# Sheet1.net
KiCad netlist of a schematic drawn in Altium Designer
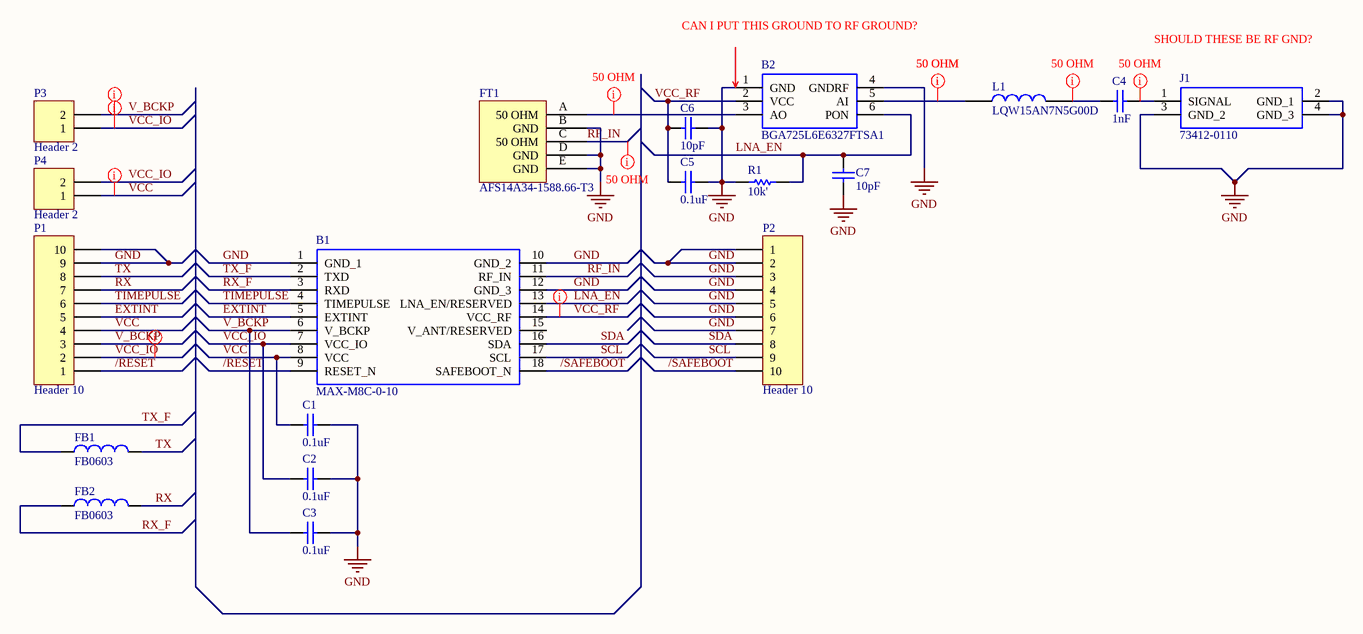
[diagram p0: Sheet1.SchDoc]

(export (version "E")
  (design (tool "Eeschema 10.0.6"))
  (components
    (comp (ref "B1")
      (value "MAX-M8C-0-10")
      (footprint "MAX-M8")
      (description "u-blox M8 concurrent GNSS module")
      (libsource (lib "MAX-M8C-0-10") (part "MAX-M8C-0-10"))
    )
    (comp (ref "B2")
      (value "BGA725L6E6327FTSA1")
      (footprint "BGS12SN6E6327XTSA1")
      (description "INFINEON - BGA725L6E6327FTSA1 - RF AMP, 20DB, 1.615GHZ, 3.6V, TSLP-6")
      (fields (field (name "MOUSER PART NUMBER") "726-BGA725L6E6327FTS"))
      (libsource (lib "BGA725L6E6327FTSA1") (part "BGA725L6E6327FTSA1"))
    )
    (comp (ref "C1")
      (value "0.1uF")
      (footprint "0603CAP")
      (description "0603 Ceramic Chip Capacitor - Standard")
      (fields (field (name "Comment") "C0603"))
      (libsource (lib "Standard Components") (part "C0603"))
    )
    (comp (ref "C2")
      (value "0.1uF")
      (footprint "0603CAP")
      (description "0603 Ceramic Chip Capacitor - Standard")
      (fields (field (name "Comment") "C0603"))
      (libsource (lib "Standard Components") (part "C0603"))
    )
    (comp (ref "C3")
      (value "0.1uF")
      (footprint "0603CAP")
      (description "0603 Ceramic Chip Capacitor - Standard")
      (fields (field (name "Comment") "C0603"))
      (libsource (lib "Standard Components") (part "C0603"))
    )
    (comp (ref "C4")
      (value "1nF")
      (footprint "0603CAP")
      (description "0603 Ceramic Chip Capacitor - Standard")
      (fields (field (name "Comment") "C0603"))
      (libsource (lib "Standard Components") (part "C0603"))
    )
    (comp (ref "C5")
      (value "0.1uF")
      (footprint "0603CAP")
      (description "0603 Ceramic Chip Capacitor - Standard")
      (fields (field (name "Comment") "C0603"))
      (libsource (lib "Standard Components") (part "C0603"))
    )
    (comp (ref "C6")
      (value "10pF")
      (footprint "0603CAP")
      (description "0603 Ceramic Chip Capacitor - Standard")
      (fields (field (name "Comment") "C0603"))
      (libsource (lib "Standard Components") (part "C0603"))
    )
    (comp (ref "C7")
      (value "10pF")
      (footprint "0603CAP")
      (description "0603 Ceramic Chip Capacitor - Standard")
      (fields (field (name "Comment") "C0603"))
      (libsource (lib "Standard Components") (part "C0603"))
    )
    (comp (ref "FB1")
      (value "FB0603")
      (footprint "0603CAP")
      (description "0603 Multilayer Ferrite Power Bead")
      (fields (field (name "MANUFACTURER") "KOA Speer"))
      (libsource (lib "Standard Components") (part "FB0603"))
    )
    (comp (ref "FB2")
      (value "FB0603")
      (footprint "0603CAP")
      (description "0603 Multilayer Ferrite Power Bead")
      (fields (field (name "MANUFACTURER") "KOA Speer"))
      (libsource (lib "Standard Components") (part "FB0603"))
    )
    (comp (ref "FT1")
      (value "AFS14A34-1588.66-T3")
      (footprint "AFS14A34-1588.66-T3")
      (description "SAW FILTER")
      (fields (field (name "MANUFACTURER") "Abracon LLC"))
      (libsource (lib "myLib") (part "AFS14A34-1588.66-T3"))
    )
    (comp (ref "J1")
      (value "73412-0110")
      (footprint "73412-0110")
      (description "50 Ohms, MCRF, PCB Vertical Jack Receptacle, SMT, 1.25mm Mounted Height")
      (fields (field (name "RS PART NUMBER") "1676350") (field (name "MOUSER PART NUMBER") "538-73412-0110"))
      (libsource (lib "73412-0110") (part "73412-0110"))
    )
    (comp (ref "L1")
      (value "LQW15AN7N5G00D")
      (footprint "INDC1005X55N")
      (fields
        (field (name "RS PART NUMBER") "7926473P")
        (field (name "MOUSER PART NUMBER") "81-LQW15AN7N5G00D")
      )
      (libsource (lib "LQW15AN7N5G00D") (part "LQW15AN7N5G00D"))
    )
    (comp (ref "P1")
      (value "Header 10")
      (footprint "HDR1X10")
      (description "Header, 10-Pin")
      (fields (field (name "PUBLISHER") "Altium Limited"))
      (libsource (lib "") (part "Header 10_1"))
    )
    (comp (ref "P2")
      (value "Header 10")
      (footprint "HDR1X10")
      (description "Header, 10-Pin")
      (fields (field (name "PUBLISHER") "Altium Limited"))
      (libsource (lib "Miscellaneous Connectors") (part "Header 10"))
    )
    (comp (ref "P3")
      (value "Header 2")
      (footprint "HDR1X2")
      (description "Header, 2-Pin")
      (fields (field (name "PUBLISHER") "Altium Limited"))
      (libsource (lib "Miscellaneous Connectors") (part "Header 2"))
    )
    (comp (ref "P4")
      (value "Header 2")
      (footprint "HDR1X2")
      (description "Header, 2-Pin")
      (fields (field (name "PUBLISHER") "Altium Limited"))
      (libsource (lib "Miscellaneous Connectors") (part "Header 2"))
    )
    (comp (ref "R1")
      (value "10k'")
      (footprint "0603RES")
      (description "0603 Chip Resistor - Standard")
      (fields (field (name "Comment") "R0603"))
      (libsource (lib "Standard Components") (part "R0603"))
    )
  )
  (nets
    (net (code "1") (name "/EXTINT") (class "Default")
      (node (ref "B1") (pin "5") (pinfunction "EXTINT_5") (pintype "passive"))
      (node (ref "P1") (pin "5") (pinfunction "5_5") (pintype "passive"))
    )
    (net (code "2") (name "/LNA_EN") (class "Default")
      (node (ref "B1") (pin "13") (pinfunction "LNA_EN/RESERVED_13") (pintype "passive"))
      (node (ref "B2") (pin "6") (pinfunction "PON_6") (pintype "passive"))
      (node (ref "C7") (pin "2") (pinfunction "2_2") (pintype "passive"))
      (node (ref "R1") (pin "2") (pinfunction "2_2") (pintype "passive"))
    )
    (net (code "3") (name "/RF_IN") (class "Default")
      (node (ref "B1") (pin "11") (pinfunction "RF_IN_11") (pintype "passive"))
      (node (ref "FT1") (pin "C") (pinfunction "50_OHM_C") (pintype "passive"))
    )
    (net (code "4") (name "/RX") (class "Default")
      (node (ref "FB2") (pin "2") (pinfunction "2_2") (pintype "passive"))
      (node (ref "P1") (pin "7") (pinfunction "7_7") (pintype "passive"))
    )
    (net (code "5") (name "/RX_F") (class "Default")
      (node (ref "B1") (pin "3") (pinfunction "RXD_3") (pintype "passive"))
      (node (ref "FB2") (pin "1") (pinfunction "1_1") (pintype "passive"))
    )
    (net (code "6") (name "/SCL") (class "Default")
      (node (ref "B1") (pin "17") (pinfunction "SCL_17") (pintype "passive"))
      (node (ref "P2") (pin "9") (pinfunction "9_9") (pintype "passive"))
    )
    (net (code "7") (name "/SDA") (class "Default")
      (node (ref "B1") (pin "16") (pinfunction "SDA_16") (pintype "passive"))
      (node (ref "P2") (pin "8") (pinfunction "8_8") (pintype "passive"))
    )
    (net (code "8") (name "/TIMEPULSE") (class "Default")
      (node (ref "B1") (pin "4") (pinfunction "TIMEPULSE_4") (pintype "passive"))
      (node (ref "P1") (pin "6") (pinfunction "6_6") (pintype "passive"))
    )
    (net (code "9") (name "/TX") (class "Default")
      (node (ref "FB1") (pin "2") (pinfunction "2_2") (pintype "passive"))
      (node (ref "P1") (pin "8") (pinfunction "8_8") (pintype "passive"))
    )
    (net (code "10") (name "/TX_F") (class "Default")
      (node (ref "B1") (pin "2") (pinfunction "TXD_2") (pintype "passive"))
      (node (ref "FB1") (pin "1") (pinfunction "1_1") (pintype "passive"))
    )
    (net (code "11") (name "/VCC") (class "Default")
      (node (ref "B1") (pin "8") (pinfunction "VCC_8") (pintype "passive"))
      (node (ref "C1") (pin "1") (pinfunction "1_1") (pintype "passive"))
      (node (ref "P1") (pin "4") (pinfunction "4_4") (pintype "passive"))
      (node (ref "P4") (pin "1") (pinfunction "1_1") (pintype "passive"))
    )
    (net (code "12") (name "/VCC_IO") (class "Default")
      (node (ref "B1") (pin "7") (pinfunction "VCC_IO_7") (pintype "passive"))
      (node (ref "C2") (pin "1") (pinfunction "1_1") (pintype "passive"))
      (node (ref "P1") (pin "2") (pinfunction "2_2") (pintype "passive"))
      (node (ref "P3") (pin "1") (pinfunction "1_1") (pintype "passive"))
      (node (ref "P4") (pin "2") (pinfunction "2_2") (pintype "passive"))
    )
    (net (code "13") (name "/VCC_RF") (class "Default")
      (node (ref "B1") (pin "14") (pinfunction "VCC_RF_14") (pintype "passive"))
      (node (ref "B2") (pin "2") (pinfunction "VCC_2") (pintype "passive"))
      (node (ref "C5") (pin "1") (pinfunction "1_1") (pintype "passive"))
      (node (ref "C6") (pin "1") (pinfunction "1_1") (pintype "passive"))
    )
    (net (code "14") (name "/V_BCKP") (class "Default")
      (node (ref "B1") (pin "6") (pinfunction "V_BCKP_6") (pintype "passive"))
      (node (ref "C3") (pin "1") (pinfunction "1_1") (pintype "passive"))
      (node (ref "P1") (pin "3") (pinfunction "3_3") (pintype "passive"))
      (node (ref "P3") (pin "2") (pinfunction "2_2") (pintype "passive"))
    )
    (net (code "15") (name "/{slash}RESET") (class "Default")
      (node (ref "B1") (pin "9") (pinfunction "RESET_N_9") (pintype "passive"))
      (node (ref "P1") (pin "1") (pinfunction "1_1") (pintype "passive"))
    )
    (net (code "16") (name "/{slash}SAFEBOOT") (class "Default")
      (node (ref "B1") (pin "18") (pinfunction "SAFEBOOT_N_18") (pintype "passive"))
      (node (ref "P2") (pin "10") (pinfunction "10_10") (pintype "passive"))
    )
    (net (code "17") (name "GND") (class "Default")
      (node (ref "B1") (pin "1") (pinfunction "GND_1_1") (pintype "passive"))
      (node (ref "B1") (pin "10") (pinfunction "GND_2_10") (pintype "passive"))
      (node (ref "B1") (pin "12") (pinfunction "GND_3_12") (pintype "passive"))
      (node (ref "B2") (pin "1") (pinfunction "GND_1") (pintype "passive"))
      (node (ref "B2") (pin "4") (pinfunction "GNDRF_4") (pintype "passive"))
      (node (ref "C1") (pin "2") (pinfunction "2_2") (pintype "passive"))
      (node (ref "C2") (pin "2") (pinfunction "2_2") (pintype "passive"))
      (node (ref "C3") (pin "2") (pinfunction "2_2") (pintype "passive"))
      (node (ref "C5") (pin "2") (pinfunction "2_2") (pintype "passive"))
      (node (ref "C6") (pin "2") (pinfunction "2_2") (pintype "passive"))
      (node (ref "C7") (pin "1") (pinfunction "1_1") (pintype "passive"))
      (node (ref "FT1") (pin "B") (pinfunction "GND_B") (pintype "passive"))
      (node (ref "FT1") (pin "D") (pinfunction "GND_D") (pintype "passive"))
      (node (ref "FT1") (pin "E") (pinfunction "GND_E") (pintype "passive"))
      (node (ref "J1") (pin "2") (pinfunction "GND_1_2") (pintype "passive"))
      (node (ref "J1") (pin "3") (pinfunction "GND_2_3") (pintype "passive"))
      (node (ref "J1") (pin "4") (pinfunction "GND_3_4") (pintype "passive"))
      (node (ref "P1") (pin "10") (pinfunction "10_10") (pintype "passive"))
      (node (ref "P1") (pin "9") (pinfunction "9_9") (pintype "passive"))
      (node (ref "P2") (pin "1") (pinfunction "1_1") (pintype "passive"))
      (node (ref "P2") (pin "2") (pinfunction "2_2") (pintype "passive"))
      (node (ref "P2") (pin "3") (pinfunction "3_3") (pintype "passive"))
      (node (ref "P2") (pin "4") (pinfunction "4_4") (pintype "passive"))
      (node (ref "P2") (pin "5") (pinfunction "5_5") (pintype "passive"))
      (node (ref "P2") (pin "6") (pinfunction "6_6") (pintype "passive"))
      (node (ref "P2") (pin "7") (pinfunction "7_7") (pintype "passive"))
      (node (ref "R1") (pin "1") (pinfunction "1_1") (pintype "passive"))
    )
    (net (code "18") (name "Net-(B2-AI)") (class "Default")
      (node (ref "B2") (pin "5") (pinfunction "AI_5") (pintype "passive"))
      (node (ref "L1") (pin "1") (pinfunction "1_1") (pintype "passive"))
    )
    (net (code "19") (name "Net-(B2-AO)") (class "Default")
      (node (ref "B2") (pin "3") (pinfunction "AO_3") (pintype "passive"))
      (node (ref "FT1") (pin "A") (pinfunction "50_OHM_A") (pintype "passive"))
    )
    (net (code "20") (name "Net-(C4-Pad1)") (class "Default")
      (node (ref "C4") (pin "1") (pinfunction "1_1") (pintype "passive"))
      (node (ref "L1") (pin "2") (pinfunction "2_2") (pintype "passive"))
    )
    (net (code "21") (name "Net-(J1-SIGNAL)") (class "Default")
      (node (ref "C4") (pin "2") (pinfunction "2_2") (pintype "passive"))
      (node (ref "J1") (pin "1") (pinfunction "SIGNAL_1") (pintype "passive"))
    )
    (net (code "22") (name "unconnected-(B1-V_ANT{slash}RESERVED-Pad15)") (class "Default")
      (node (ref "B1") (pin "15") (pinfunction "V_ANT/RESERVED_15") (pintype "passive"))
    )
  )
)
